# AAA_Battery_Shield.net
KiCad netlist of a schematic drawn in EAGLE
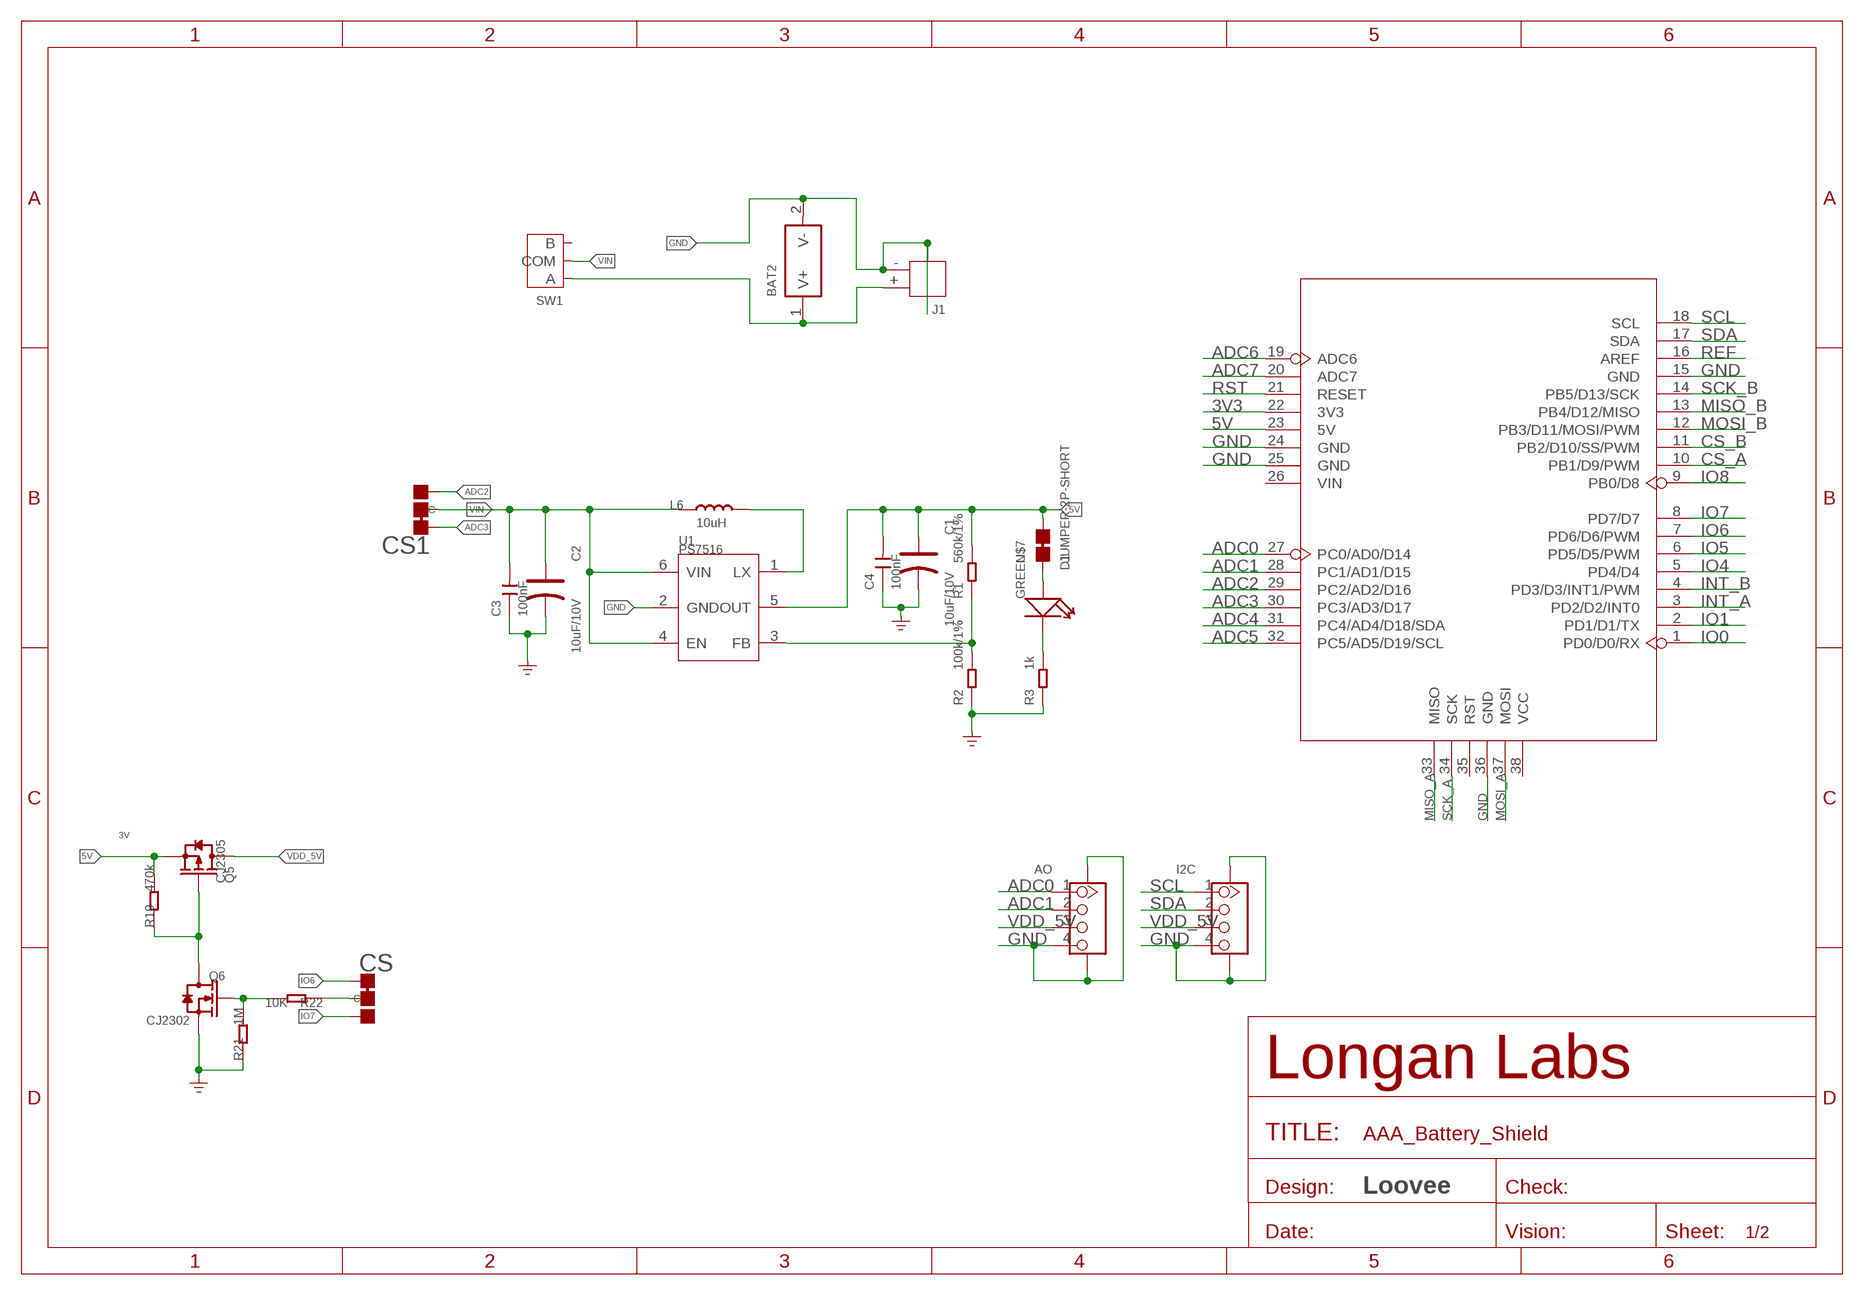
[diagram p0: schematic, sheet 1]

(export (version "E")
  (design (tool "Eeschema 10.0.6"))
  (components
    (comp (ref "AO")
      (value "GROVE-CONNECTOR-SMD'90D'")
      (footprint "eagle-import:HW4-SMD-2.0-90D")
      (libsource (lib "eagle-import") (part "GROVE-CONNECTOR-SMD'90D'"))
    )
    (comp (ref "BAT2")
      (value "BAT-HOLDER-BC2AAA")
      (footprint "eagle-import:BAT2P-12.5-51.8X24MM")
      (libsource (lib "eagle-import") (part "BAT-HOLDER-BC2AAA"))
    )
    (comp (ref "C1")
      (value "10uF/10V")
      (footprint "eagle-import:AVX-B")
      (libsource (lib "eagle-import") (part "CAP-POLAR-AVX-B"))
    )
    (comp (ref "C2")
      (value "10uF/10V")
      (footprint "eagle-import:AVX-B")
      (libsource (lib "eagle-import") (part "CAP-POLAR-AVX-B"))
    )
    (comp (ref "C3")
      (value "100nF")
      (footprint "eagle-import:C0603")
      (libsource (lib "eagle-import") (part "CAP-0603"))
    )
    (comp (ref "C4")
      (value "100nF")
      (footprint "eagle-import:C0603")
      (libsource (lib "eagle-import") (part "CAP-0603"))
    )
    (comp (ref "CS")
      (value "JUMPER-3P-SHORT")
      (footprint "eagle-import:3P-SMD-SHORT")
      (libsource (lib "eagle-import") (part "JUMPER-3P-SHORT"))
    )
    (comp (ref "CS1")
      (value "JUMPER-3P-SHORT")
      (footprint "eagle-import:3P-SMD-SHORT")
      (libsource (lib "eagle-import") (part "JUMPER-3P-SHORT"))
    )
    (comp (ref "D1")
      (value "GREEN")
      (footprint "eagle-import:LED-0603")
      (libsource (lib "eagle-import") (part "LED'0603'"))
    )
    (comp (ref "I2C")
      (value "GROVE-CONNECTOR-SMD'90D'")
      (footprint "eagle-import:HW4-SMD-2.0-90D")
      (libsource (lib "eagle-import") (part "GROVE-CONNECTOR-SMD'90D'"))
    )
    (comp (ref "J1")
      (value "JST-2P-SMD'2.0'")
      (footprint "eagle-import:HW2-SMD-2.0-90D")
      (libsource (lib "eagle-import") (part "JST-2P-SMD'2.0'"))
    )
    (comp (ref "L6")
      (value "10uH")
      (footprint "eagle-import:L0420")
      (libsource (lib "eagle-import") (part "LSPD3D16-4R7M"))
    )
    (comp (ref "Q5")
      (value "CJ2305")
      (footprint "eagle-import:SOT-23")
      (libsource (lib "eagle-import") (part "MOSFET-P'SI2323CDS/SI2305DS{lt}BR{gt}'"))
    )
    (comp (ref "Q6")
      (value "CJ2302")
      (footprint "eagle-import:SOT-23")
      (libsource (lib "eagle-import") (part "MOSFET-N'SOT23'"))
    )
    (comp (ref "R1")
      (value "560k/1%")
      (footprint "eagle-import:R0603")
      (libsource (lib "eagle-import") (part "RES-0603"))
    )
    (comp (ref "R2")
      (value "100k/1%")
      (footprint "eagle-import:R0603")
      (libsource (lib "eagle-import") (part "RES-0603"))
    )
    (comp (ref "R3")
      (value "1k")
      (footprint "eagle-import:R0603")
      (libsource (lib "eagle-import") (part "RES-0603"))
    )
    (comp (ref "R19")
      (value "470k")
      (footprint "eagle-import:R0603")
      (libsource (lib "eagle-import") (part "RES-0603"))
    )
    (comp (ref "R21")
      (value "1M")
      (footprint "eagle-import:R0603")
      (libsource (lib "eagle-import") (part "RES-0603"))
    )
    (comp (ref "R22")
      (value "10K")
      (footprint "eagle-import:R0603")
      (libsource (lib "eagle-import") (part "RES-0603"))
    )
    (comp (ref "SW1")
      (value "SWITCH-2H-3P")
      (footprint "eagle-import:SW3-2.5-9X3.5MM")
      (libsource (lib "eagle-import") (part "SWITCH-2H-3P"))
    )
    (comp (ref "U$7")
      (value "JUMPER-2P-SHORT")
      (footprint "eagle-import:2P-SMD-SHORT")
      (libsource (lib "eagle-import") (part "JUMPER-2P-SHORT"))
    )
    (comp (ref "U1")
      (value "PS7516")
      (footprint "eagle-import:SOT-23-6")
      (libsource (lib "eagle-import") (part "PMIC-PS7516"))
    )
    (comp (ref "U4")
      (value "ARDUINO-38P'WITH/-SILK'")
      (footprint "eagle-import:ARDUINO-38P-WITH_-SILK-500519002")
      (libsource (lib "eagle-import") (part "ARDUINO-38P'WITH/-SILK'"))
    )
  )
  (nets
    (net (code "1") (name "3V3") (class "Default")
      (node (ref "U4") (pin "22") (pinfunction "3V3_22") (pintype "bidirectional"))
    )
    (net (code "2") (name "5V") (class "Default")
      (node (ref "C1") (pin "+") (pinfunction "+_+") (pintype "passive"))
      (node (ref "C4") (pin "2") (pinfunction "2_2") (pintype "passive"))
      (node (ref "Q5") (pin "2") (pinfunction "S_2") (pintype "passive"))
      (node (ref "R1") (pin "2") (pinfunction "2_2") (pintype "passive"))
      (node (ref "R19") (pin "2") (pinfunction "2_2") (pintype "passive"))
      (node (ref "U$7") (pin "2") (pinfunction "2_2") (pintype "bidirectional"))
      (node (ref "U1") (pin "5") (pinfunction "OUT_5") (pintype "bidirectional"))
      (node (ref "U4") (pin "23") (pinfunction "5V_23") (pintype "bidirectional"))
    )
    (net (code "3") (name "ADC0") (class "Default")
      (node (ref "AO") (pin "1") (pinfunction "1_1") (pintype "bidirectional"))
      (node (ref "U4") (pin "27") (pinfunction "PC0/AD0/D14_27") (pintype "bidirectional"))
    )
    (net (code "4") (name "ADC1") (class "Default")
      (node (ref "AO") (pin "2") (pinfunction "2_2") (pintype "bidirectional"))
      (node (ref "U4") (pin "28") (pinfunction "PC1/AD1/D15_28") (pintype "bidirectional"))
    )
    (net (code "5") (name "ADC2") (class "Default")
      (node (ref "CS1") (pin "00") (pinfunction "R_00") (pintype "bidirectional"))
      (node (ref "U4") (pin "29") (pinfunction "PC2/AD2/D16_29") (pintype "bidirectional"))
    )
    (net (code "6") (name "ADC3") (class "Default")
      (node (ref "CS1") (pin "11") (pinfunction "L_11") (pintype "bidirectional"))
      (node (ref "U4") (pin "30") (pinfunction "PC3/AD3/D17_30") (pintype "bidirectional"))
    )
    (net (code "7") (name "ADC4") (class "Default")
      (node (ref "U4") (pin "31") (pinfunction "PC4/AD4/D18/SDA_31") (pintype "bidirectional"))
    )
    (net (code "8") (name "ADC5") (class "Default")
      (node (ref "U4") (pin "32") (pinfunction "PC5/AD5/D19/SCL_32") (pintype "bidirectional"))
    )
    (net (code "9") (name "ADC6") (class "Default")
      (node (ref "U4") (pin "19") (pinfunction "ADC6_19") (pintype "bidirectional"))
    )
    (net (code "10") (name "ADC7") (class "Default")
      (node (ref "U4") (pin "20") (pinfunction "ADC7_20") (pintype "bidirectional"))
    )
    (net (code "11") (name "CS_A") (class "Default")
      (node (ref "U4") (pin "10") (pinfunction "PB1/D9/PWM_10") (pintype "bidirectional"))
    )
    (net (code "12") (name "CS_B") (class "Default")
      (node (ref "U4") (pin "11") (pinfunction "PB2/D10/SS/PWM_11") (pintype "bidirectional"))
    )
    (net (code "13") (name "GND") (class "Default")
      (node (ref "AO") (pin "4") (pinfunction "4_4") (pintype "bidirectional"))
      (node (ref "AO") (pin "SS1") (pinfunction "SS1_SS1") (pintype "bidirectional"))
      (node (ref "AO") (pin "SS2") (pinfunction "SS2_SS2") (pintype "bidirectional"))
      (node (ref "BAT2") (pin "2") (pinfunction "V-_2") (pintype "bidirectional"))
      (node (ref "C1") (pin "-") (pinfunction "-_-") (pintype "passive"))
      (node (ref "C2") (pin "-") (pinfunction "-_-") (pintype "passive"))
      (node (ref "C3") (pin "1") (pinfunction "1_1") (pintype "passive"))
      (node (ref "C4") (pin "1") (pinfunction "1_1") (pintype "passive"))
      (node (ref "I2C") (pin "4") (pinfunction "4_4") (pintype "bidirectional"))
      (node (ref "I2C") (pin "SS1") (pinfunction "SS1_SS1") (pintype "bidirectional"))
      (node (ref "I2C") (pin "SS2") (pinfunction "SS2_SS2") (pintype "bidirectional"))
      (node (ref "J1") (pin "-") (pinfunction "2_-") (pintype "bidirectional"))
      (node (ref "J1") (pin "3") (pinfunction "3_3") (pintype "bidirectional"))
      (node (ref "J1") (pin "4") (pinfunction "4_4") (pintype "bidirectional"))
      (node (ref "Q6") (pin "2") (pinfunction "S_2") (pintype "passive"))
      (node (ref "R2") (pin "1") (pinfunction "1_1") (pintype "passive"))
      (node (ref "R21") (pin "1") (pinfunction "1_1") (pintype "passive"))
      (node (ref "R3") (pin "1") (pinfunction "1_1") (pintype "passive"))
      (node (ref "U1") (pin "2") (pinfunction "GND_2") (pintype "bidirectional"))
      (node (ref "U4") (pin "15") (pinfunction "GND_15") (pintype "bidirectional"))
      (node (ref "U4") (pin "24") (pinfunction "GND_24") (pintype "bidirectional"))
      (node (ref "U4") (pin "25") (pinfunction "GND_25") (pintype "bidirectional"))
      (node (ref "U4") (pin "36") (pinfunction "GND_36") (pintype "bidirectional"))
    )
    (net (code "14") (name "INT_A") (class "Default")
      (node (ref "U4") (pin "3") (pinfunction "PD2/D2/INT0_3") (pintype "bidirectional"))
    )
    (net (code "15") (name "INT_B") (class "Default")
      (node (ref "U4") (pin "4") (pinfunction "PD3/D3/INT1/PWM_4") (pintype "bidirectional"))
    )
    (net (code "16") (name "IO0") (class "Default")
      (node (ref "U4") (pin "1") (pinfunction "PD0/D0/RX_1") (pintype "bidirectional"))
    )
    (net (code "17") (name "IO1") (class "Default")
      (node (ref "U4") (pin "2") (pinfunction "PD1/D1/TX_2") (pintype "bidirectional"))
    )
    (net (code "18") (name "IO4") (class "Default")
      (node (ref "U4") (pin "5") (pinfunction "PD4/D4_5") (pintype "bidirectional"))
    )
    (net (code "19") (name "IO5") (class "Default")
      (node (ref "U4") (pin "6") (pinfunction "PD5/D5/PWM_6") (pintype "bidirectional"))
    )
    (net (code "20") (name "IO6") (class "Default")
      (node (ref "CS") (pin "11") (pinfunction "L_11") (pintype "bidirectional"))
      (node (ref "U4") (pin "7") (pinfunction "PD6/D6/PWM_7") (pintype "bidirectional"))
    )
    (net (code "21") (name "IO7") (class "Default")
      (node (ref "CS") (pin "00") (pinfunction "R_00") (pintype "bidirectional"))
      (node (ref "U4") (pin "8") (pinfunction "PD7/D7_8") (pintype "bidirectional"))
    )
    (net (code "22") (name "IO8") (class "Default")
      (node (ref "U4") (pin "9") (pinfunction "PB0/D8_9") (pintype "bidirectional"))
    )
    (net (code "23") (name "MISO_A") (class "Default")
      (node (ref "U4") (pin "33") (pinfunction "MISO_33") (pintype "bidirectional"))
    )
    (net (code "24") (name "MISO_B") (class "Default")
      (node (ref "U4") (pin "13") (pinfunction "PB4/D12/MISO_13") (pintype "bidirectional"))
    )
    (net (code "25") (name "MOSI_A") (class "Default")
      (node (ref "U4") (pin "37") (pinfunction "MOSI_37") (pintype "bidirectional"))
    )
    (net (code "26") (name "MOSI_B") (class "Default")
      (node (ref "U4") (pin "12") (pinfunction "PB3/D11/MOSI/PWM_12") (pintype "bidirectional"))
    )
    (net (code "27") (name "Net-(BAT2-V+)") (class "Default")
      (node (ref "BAT2") (pin "1") (pinfunction "V+_1") (pintype "bidirectional"))
      (node (ref "J1") (pin "+") (pinfunction "1_+") (pintype "bidirectional"))
      (node (ref "SW1") (pin "1") (pinfunction "A_1") (pintype "bidirectional"))
    )
    (net (code "28") (name "Net-(CS-C)") (class "Default")
      (node (ref "CS") (pin "MM") (pinfunction "C_MM") (pintype "bidirectional"))
      (node (ref "R22") (pin "1") (pinfunction "1_1") (pintype "passive"))
    )
    (net (code "29") (name "Net-(D1-Pad+)") (class "Default")
      (node (ref "D1") (pin "+") (pinfunction "+_+") (pintype "passive"))
      (node (ref "U$7") (pin "1") (pinfunction "1_1") (pintype "bidirectional"))
    )
    (net (code "30") (name "Net-(D1-Pad-)") (class "Default")
      (node (ref "D1") (pin "-") (pinfunction "-_-") (pintype "passive"))
      (node (ref "R3") (pin "2") (pinfunction "2_2") (pintype "passive"))
    )
    (net (code "31") (name "Net-(Q5-G)") (class "Default")
      (node (ref "Q5") (pin "1") (pinfunction "G_1") (pintype "passive"))
      (node (ref "Q6") (pin "3") (pinfunction "D_3") (pintype "passive"))
      (node (ref "R19") (pin "1") (pinfunction "1_1") (pintype "passive"))
    )
    (net (code "32") (name "Net-(Q6-G)") (class "Default")
      (node (ref "Q6") (pin "1") (pinfunction "G_1") (pintype "passive"))
      (node (ref "R21") (pin "2") (pinfunction "2_2") (pintype "passive"))
      (node (ref "R22") (pin "2") (pinfunction "2_2") (pintype "passive"))
    )
    (net (code "33") (name "Net-(U1-FB)") (class "Default")
      (node (ref "R1") (pin "1") (pinfunction "1_1") (pintype "passive"))
      (node (ref "R2") (pin "2") (pinfunction "2_2") (pintype "passive"))
      (node (ref "U1") (pin "3") (pinfunction "FB_3") (pintype "bidirectional"))
    )
    (net (code "34") (name "Net-(U1-LX)") (class "Default")
      (node (ref "L6") (pin "2") (pinfunction "2_2") (pintype "passive"))
      (node (ref "U1") (pin "1") (pinfunction "LX_1") (pintype "bidirectional"))
    )
    (net (code "35") (name "REF") (class "Default")
      (node (ref "U4") (pin "16") (pinfunction "AREF_16") (pintype "bidirectional"))
    )
    (net (code "36") (name "RST") (class "Default")
      (node (ref "U4") (pin "21") (pinfunction "RESET_21") (pintype "bidirectional"))
    )
    (net (code "37") (name "SCK_A") (class "Default")
      (node (ref "U4") (pin "34") (pinfunction "SCK_34") (pintype "bidirectional"))
    )
    (net (code "38") (name "SCK_B") (class "Default")
      (node (ref "U4") (pin "14") (pinfunction "PB5/D13/SCK_14") (pintype "bidirectional"))
    )
    (net (code "39") (name "SCL") (class "Default")
      (node (ref "I2C") (pin "1") (pinfunction "1_1") (pintype "bidirectional"))
      (node (ref "U4") (pin "18") (pinfunction "SCL_18") (pintype "bidirectional"))
    )
    (net (code "40") (name "SDA") (class "Default")
      (node (ref "I2C") (pin "2") (pinfunction "2_2") (pintype "bidirectional"))
      (node (ref "U4") (pin "17") (pinfunction "SDA_17") (pintype "bidirectional"))
    )
    (net (code "41") (name "VDD_5V") (class "Default")
      (node (ref "AO") (pin "3") (pinfunction "3_3") (pintype "bidirectional"))
      (node (ref "I2C") (pin "3") (pinfunction "3_3") (pintype "bidirectional"))
      (node (ref "Q5") (pin "3") (pinfunction "D_3") (pintype "passive"))
    )
    (net (code "42") (name "VIN") (class "Default")
      (node (ref "C2") (pin "+") (pinfunction "+_+") (pintype "passive"))
      (node (ref "C3") (pin "2") (pinfunction "2_2") (pintype "passive"))
      (node (ref "CS1") (pin "MM") (pinfunction "C_MM") (pintype "bidirectional"))
      (node (ref "L6") (pin "1") (pinfunction "1_1") (pintype "passive"))
      (node (ref "SW1") (pin "2") (pinfunction "COM_2") (pintype "bidirectional"))
      (node (ref "U1") (pin "4") (pinfunction "EN_4") (pintype "bidirectional"))
      (node (ref "U1") (pin "6") (pinfunction "VIN_6") (pintype "bidirectional"))
    )
    (net (code "43") (name "unconnected-(SW1-B-Pad3)") (class "Default")
      (node (ref "SW1") (pin "3") (pinfunction "B_3") (pintype "bidirectional"))
    )
    (net (code "44") (name "unconnected-(U4-RST-Pad35)") (class "Default")
      (node (ref "U4") (pin "35") (pinfunction "RST_35") (pintype "bidirectional"))
    )
    (net (code "45") (name "unconnected-(U4-VCC-Pad38)") (class "Default")
      (node (ref "U4") (pin "38") (pinfunction "VCC_38") (pintype "bidirectional"))
    )
    (net (code "46") (name "unconnected-(U4-VIN-Pad26)") (class "Default")
      (node (ref "U4") (pin "26") (pinfunction "VIN_26") (pintype "bidirectional"))
    )
  )
)
